# Reset_Handler.net
KiCad netlist of a schematic drawn in EAGLE
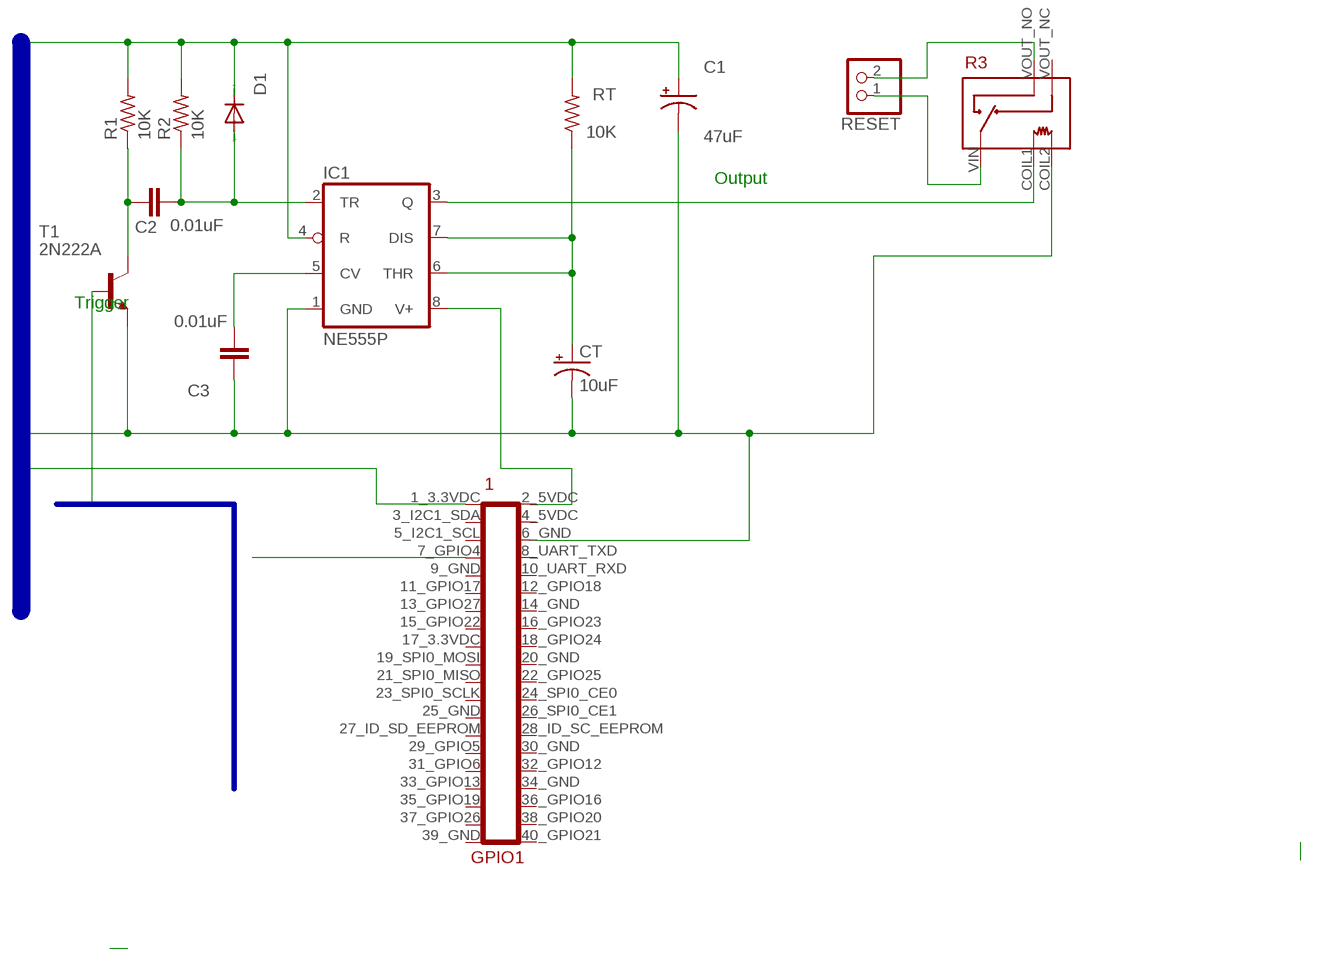
[diagram p0: schematic, sheet 1]

(export (version "E")
  (design (tool "Eeschema 10.0.6"))
  (components
    (comp (ref "C1")
      (value "47uF")
      (footprint "eagle-import:E2,5-5")
      (libsource (lib "eagle-import") (part "CPOL-USE2.5-5"))
    )
    (comp (ref "C2")
      (value "0.01uF")
      (footprint "eagle-import:C10B4")
      (libsource (lib "eagle-import") (part "C10/4"))
    )
    (comp (ref "C3")
      (value "0.01uF")
      (footprint "eagle-import:C10B4")
      (libsource (lib "eagle-import") (part "C10/4"))
    )
    (comp (ref "CT")
      (value "10uF")
      (footprint "eagle-import:E2,5-5")
      (libsource (lib "eagle-import") (part "CPOL-USE2.5-5"))
    )
    (comp (ref "D1")
      (value "1N4148")
      (footprint "eagle-import:DO35-7")
      (libsource (lib "eagle-import") (part "1N4148DO35-7"))
    )
    (comp (ref "GPIO1")
      (value "RPI_GPIO_MALE_OPEN")
      (footprint "eagle-import:RPI_GPIO_FEMALE_TOP")
      (libsource (lib "eagle-import") (part "RPI_GPIO_MALE_OPEN"))
    )
    (comp (ref "IC1")
      (value "NE555P")
      (footprint "eagle-import:DIL08")
      (libsource (lib "eagle-import") (part "555PNE"))
    )
    (comp (ref "R1")
      (value "10K")
      (footprint "eagle-import:0207_10")
      (libsource (lib "eagle-import") (part "R-US_0207/10"))
    )
    (comp (ref "R2")
      (value "10K")
      (footprint "eagle-import:0207_10")
      (libsource (lib "eagle-import") (part "R-US_0207/10"))
    )
    (comp (ref "R3")
      (value "5VDC")
      (footprint "eagle-import:OUAZ-SS1_")
      (libsource (lib "eagle-import") (part "OUAZ-OUAZ-SS-105D"))
    )
    (comp (ref "RESET")
      (value "PINHD-1X2")
      (footprint "eagle-import:1X02")
      (libsource (lib "eagle-import") (part "PINHD-1X2"))
    )
    (comp (ref "RT")
      (value "10K")
      (footprint "eagle-import:0207_10")
      (libsource (lib "eagle-import") (part "R-US_0207/10"))
    )
    (comp (ref "T1")
      (value "2N222A")
      (footprint "eagle-import:TO92-EBC")
      (libsource (lib "eagle-import") (part "-NPN-TO92-EBC2N2222"))
    )
  )
  (nets
    (net (code "1") (name "/+3.3VDC") (class "Default")
      (node (ref "C1") (pin "+") (pinfunction "+_+") (pintype "passive"))
      (node (ref "D1") (pin "C") (pinfunction "C_C") (pintype "passive"))
      (node (ref "GPIO1") (pin "1_3.3VDC") (pinfunction "1_3.3VDC_1_3.3VDC") (pintype "power_in"))
      (node (ref "IC1") (pin "4") (pinfunction "R_4") (pintype "input"))
      (node (ref "R1") (pin "2") (pinfunction "2_2") (pintype "passive"))
      (node (ref "R2") (pin "2") (pinfunction "2_2") (pintype "passive"))
      (node (ref "RT") (pin "2") (pinfunction "2_2") (pintype "passive"))
    )
    (net (code "2") (name "/4_5VDC") (class "Default")
      (node (ref "GPIO1") (pin "4_5VDC") (pinfunction "4_5VDC_4_5VDC") (pintype "power_in"))
    )
    (net (code "3") (name "/9_GND") (class "Default")
      (node (ref "GPIO1") (pin "9_GND") (pinfunction "9_GND_9_GND") (pintype "power_in"))
    )
    (net (code "4") (name "/14_GND") (class "Default")
      (node (ref "GPIO1") (pin "14_GND") (pinfunction "14_GND_14_GND") (pintype "power_in"))
    )
    (net (code "5") (name "/17_3.3VDC") (class "Default")
      (node (ref "GPIO1") (pin "17_3.3VDC") (pinfunction "17_3.3VDC_17_3.3VDC") (pintype "power_in"))
    )
    (net (code "6") (name "/20_GND") (class "Default")
      (node (ref "GPIO1") (pin "20_GND") (pinfunction "20_GND_20_GND") (pintype "power_in"))
    )
    (net (code "7") (name "/25_GND") (class "Default")
      (node (ref "GPIO1") (pin "25_GND") (pinfunction "25_GND_25_GND") (pintype "power_in"))
    )
    (net (code "8") (name "/30_GND") (class "Default")
      (node (ref "GPIO1") (pin "30_GND") (pinfunction "30_GND_30_GND") (pintype "power_in"))
    )
    (net (code "9") (name "/34_GND") (class "Default")
      (node (ref "GPIO1") (pin "34_GND") (pinfunction "34_GND_34_GND") (pintype "power_in"))
    )
    (net (code "10") (name "/39_GND") (class "Default")
      (node (ref "GPIO1") (pin "39_GND") (pinfunction "39_GND_39_GND") (pintype "power_in"))
    )
    (net (code "11") (name "/GPIO_4") (class "Default")
      (node (ref "GPIO1") (pin "7_GPIO4") (pinfunction "7_GPIO4_7_GPIO4") (pintype "bidirectional"))
      (node (ref "T1") (pin "B") (pinfunction "B_B") (pintype "passive"))
    )
    (net (code "12") (name "Net-(C2-Pad2)") (class "Default")
      (node (ref "C2") (pin "2") (pinfunction "2_2") (pintype "passive"))
      (node (ref "R1") (pin "1") (pinfunction "1_1") (pintype "passive"))
      (node (ref "T1") (pin "C") (pinfunction "C_C") (pintype "passive"))
    )
    (net (code "13") (name "Net-(IC1-CV)") (class "Default")
      (node (ref "C3") (pin "2") (pinfunction "2_2") (pintype "passive"))
      (node (ref "IC1") (pin "5") (pinfunction "CV_5") (pintype "input"))
    )
    (net (code "14") (name "Net-(IC1-DIS)") (class "Default")
      (node (ref "CT") (pin "+") (pinfunction "+_+") (pintype "passive"))
      (node (ref "IC1") (pin "6") (pinfunction "THR_6") (pintype "input"))
      (node (ref "IC1") (pin "7") (pinfunction "DIS_7") (pintype "input"))
      (node (ref "RT") (pin "1") (pinfunction "1_1") (pintype "passive"))
    )
    (net (code "15") (name "Net-(IC1-GND)") (class "Default")
      (node (ref "C1") (pin "-") (pinfunction "-_-") (pintype "passive"))
      (node (ref "C3") (pin "1") (pinfunction "1_1") (pintype "passive"))
      (node (ref "CT") (pin "-") (pinfunction "-_-") (pintype "passive"))
      (node (ref "GPIO1") (pin "6_GND") (pinfunction "6_GND_6_GND") (pintype "power_in"))
      (node (ref "IC1") (pin "1") (pinfunction "GND_1") (pintype "power_in"))
      (node (ref "R3") (pin "COIL2") (pinfunction "COIL2_COIL2") (pintype "power_in"))
      (node (ref "T1") (pin "E") (pinfunction "E_E") (pintype "passive"))
    )
    (net (code "16") (name "Net-(IC1-Q)") (class "Default")
      (node (ref "IC1") (pin "3") (pinfunction "Q_3") (pintype "output"))
      (node (ref "R3") (pin "COIL1") (pinfunction "COIL1_COIL1") (pintype "power_in"))
    )
    (net (code "17") (name "Net-(IC1-TR)") (class "Default")
      (node (ref "C2") (pin "1") (pinfunction "1_1") (pintype "passive"))
      (node (ref "D1") (pin "A") (pinfunction "A_A") (pintype "passive"))
      (node (ref "IC1") (pin "2") (pinfunction "TR_2") (pintype "input"))
      (node (ref "R2") (pin "1") (pinfunction "1_1") (pintype "passive"))
    )
    (net (code "18") (name "Net-(IC1-V+)") (class "Default")
      (node (ref "GPIO1") (pin "2_5VDC") (pinfunction "2_5VDC_2_5VDC") (pintype "power_in"))
      (node (ref "IC1") (pin "8") (pinfunction "V+_8") (pintype "power_in"))
    )
    (net (code "19") (name "Net-(R3-PadVIN)") (class "Default")
      (node (ref "R3") (pin "VIN") (pinfunction "VIN_VIN") (pintype "bidirectional"))
      (node (ref "RESET") (pin "1") (pinfunction "1_1") (pintype "passive"))
    )
    (net (code "20") (name "Net-(R3-PadVOUT_NO)") (class "Default")
      (node (ref "R3") (pin "VOUT_NO") (pinfunction "VOUT_NO_VOUT_NO") (pintype "bidirectional"))
      (node (ref "RESET") (pin "2") (pinfunction "2_2") (pintype "passive"))
    )
    (net (code "21") (name "unconnected-(GPIO1-8_UART0_TXD-Pad8_UART_TXD)") (class "Default")
      (node (ref "GPIO1") (pin "8_UART_TXD") (pinfunction "8_UART0_TXD_8_UART_TXD") (pintype "bidirectional"))
    )
    (net (code "22") (name "unconnected-(GPIO1-10_UART0_RXD-Pad10_UART_RXD)") (class "Default")
      (node (ref "GPIO1") (pin "10_UART_RXD") (pinfunction "10_UART0_RXD_10_UART_RXD") (pintype "bidirectional"))
    )
    (net (code "23") (name "unconnected-(GPIO1-27_ID_SC_EEPROM-Pad27_ID_SD_EEPROM)") (class "Default")
      (node (ref "GPIO1") (pin "27_ID_SD_EEPROM") (pinfunction "27_ID_SC_EEPROM_27_ID_SD_EEPROM") (pintype "bidirectional"))
    )
    (net (code "24") (name "unconnected-(GPIO1-Pad3_I2C1_SDA)") (class "Default")
      (node (ref "GPIO1") (pin "3_I2C1_SDA") (pinfunction "3_I2C1_SDA_3_I2C1_SDA") (pintype "bidirectional"))
    )
    (net (code "25") (name "unconnected-(GPIO1-Pad5_I2C1_SCL)") (class "Default")
      (node (ref "GPIO1") (pin "5_I2C1_SCL") (pinfunction "5_I2C1_SCL_5_I2C1_SCL") (pintype "bidirectional"))
    )
    (net (code "26") (name "unconnected-(GPIO1-Pad11_GPIO17)") (class "Default")
      (node (ref "GPIO1") (pin "11_GPIO17") (pinfunction "11_GPIO17_11_GPIO17") (pintype "bidirectional"))
    )
    (net (code "27") (name "unconnected-(GPIO1-Pad12_GPIO18)") (class "Default")
      (node (ref "GPIO1") (pin "12_GPIO18") (pinfunction "12_GPIO18_12_GPIO18") (pintype "bidirectional"))
    )
    (net (code "28") (name "unconnected-(GPIO1-Pad13_GPIO27)") (class "Default")
      (node (ref "GPIO1") (pin "13_GPIO27") (pinfunction "13_GPIO27_13_GPIO27") (pintype "bidirectional"))
    )
    (net (code "29") (name "unconnected-(GPIO1-Pad15_GPIO22)") (class "Default")
      (node (ref "GPIO1") (pin "15_GPIO22") (pinfunction "15_GPIO22_15_GPIO22") (pintype "bidirectional"))
    )
    (net (code "30") (name "unconnected-(GPIO1-Pad16_GPIO23)") (class "Default")
      (node (ref "GPIO1") (pin "16_GPIO23") (pinfunction "16_GPIO23_16_GPIO23") (pintype "bidirectional"))
    )
    (net (code "31") (name "unconnected-(GPIO1-Pad18_GPIO24)") (class "Default")
      (node (ref "GPIO1") (pin "18_GPIO24") (pinfunction "18_GPIO24_18_GPIO24") (pintype "bidirectional"))
    )
    (net (code "32") (name "unconnected-(GPIO1-Pad19_SPI0_MOSI)") (class "Default")
      (node (ref "GPIO1") (pin "19_SPI0_MOSI") (pinfunction "19_SPI0_MOSI_19_SPI0_MOSI") (pintype "bidirectional"))
    )
    (net (code "33") (name "unconnected-(GPIO1-Pad21_SPI0_MISO)") (class "Default")
      (node (ref "GPIO1") (pin "21_SPI0_MISO") (pinfunction "21_SPI0_MISO_21_SPI0_MISO") (pintype "bidirectional"))
    )
    (net (code "34") (name "unconnected-(GPIO1-Pad22_GPIO25)") (class "Default")
      (node (ref "GPIO1") (pin "22_GPIO25") (pinfunction "22_GPIO25_22_GPIO25") (pintype "bidirectional"))
    )
    (net (code "35") (name "unconnected-(GPIO1-Pad23_SPI0_SCLK)") (class "Default")
      (node (ref "GPIO1") (pin "23_SPI0_SCLK") (pinfunction "23_SPI0_SCLK_23_SPI0_SCLK") (pintype "bidirectional"))
    )
    (net (code "36") (name "unconnected-(GPIO1-Pad24_SPI0_CE0)") (class "Default")
      (node (ref "GPIO1") (pin "24_SPI0_CE0") (pinfunction "24_SPI0_CE0_24_SPI0_CE0") (pintype "bidirectional"))
    )
    (net (code "37") (name "unconnected-(GPIO1-Pad26_SPI0_CE1)") (class "Default")
      (node (ref "GPIO1") (pin "26_SPI0_CE1") (pinfunction "26_SPI0_CE1_26_SPI0_CE1") (pintype "bidirectional"))
    )
    (net (code "38") (name "unconnected-(GPIO1-Pad28_ID_SC_EEPROM)") (class "Default")
      (node (ref "GPIO1") (pin "28_ID_SC_EEPROM") (pinfunction "28_ID_SC_EEPROM_28_ID_SC_EEPROM") (pintype "bidirectional"))
    )
    (net (code "39") (name "unconnected-(GPIO1-Pad29_GPIO5)") (class "Default")
      (node (ref "GPIO1") (pin "29_GPIO5") (pinfunction "29_GPIO5_29_GPIO5") (pintype "bidirectional"))
    )
    (net (code "40") (name "unconnected-(GPIO1-Pad31_GPIO6)") (class "Default")
      (node (ref "GPIO1") (pin "31_GPIO6") (pinfunction "31_GPIO6_31_GPIO6") (pintype "bidirectional"))
    )
    (net (code "41") (name "unconnected-(GPIO1-Pad32_GPIO12)") (class "Default")
      (node (ref "GPIO1") (pin "32_GPIO12") (pinfunction "32_GPIO12_32_GPIO12") (pintype "bidirectional"))
    )
    (net (code "42") (name "unconnected-(GPIO1-Pad33_GPIO13)") (class "Default")
      (node (ref "GPIO1") (pin "33_GPIO13") (pinfunction "33_GPIO13_33_GPIO13") (pintype "bidirectional"))
    )
    (net (code "43") (name "unconnected-(GPIO1-Pad35_GPIO19)") (class "Default")
      (node (ref "GPIO1") (pin "35_GPIO19") (pinfunction "35_GPIO19_35_GPIO19") (pintype "bidirectional"))
    )
    (net (code "44") (name "unconnected-(GPIO1-Pad36_GPIO16)") (class "Default")
      (node (ref "GPIO1") (pin "36_GPIO16") (pinfunction "36_GPIO16_36_GPIO16") (pintype "bidirectional"))
    )
    (net (code "45") (name "unconnected-(GPIO1-Pad37_GPIO26)") (class "Default")
      (node (ref "GPIO1") (pin "37_GPIO26") (pinfunction "37_GPIO26_37_GPIO26") (pintype "bidirectional"))
    )
    (net (code "46") (name "unconnected-(GPIO1-Pad38_GPIO20)") (class "Default")
      (node (ref "GPIO1") (pin "38_GPIO20") (pinfunction "38_GPIO20_38_GPIO20") (pintype "bidirectional"))
    )
    (net (code "47") (name "unconnected-(GPIO1-Pad40_GPIO21)") (class "Default")
      (node (ref "GPIO1") (pin "40_GPIO21") (pinfunction "40_GPIO21_40_GPIO21") (pintype "bidirectional"))
    )
    (net (code "48") (name "unconnected-(R3-PadVOUT_NC)") (class "Default")
      (node (ref "R3") (pin "VOUT_NC") (pinfunction "VOUT_NC_VOUT_NC") (pintype "bidirectional"))
    )
  )
)
